# 1206PTC-TO252.net
KiCad netlist of a schematic drawn in EAGLE
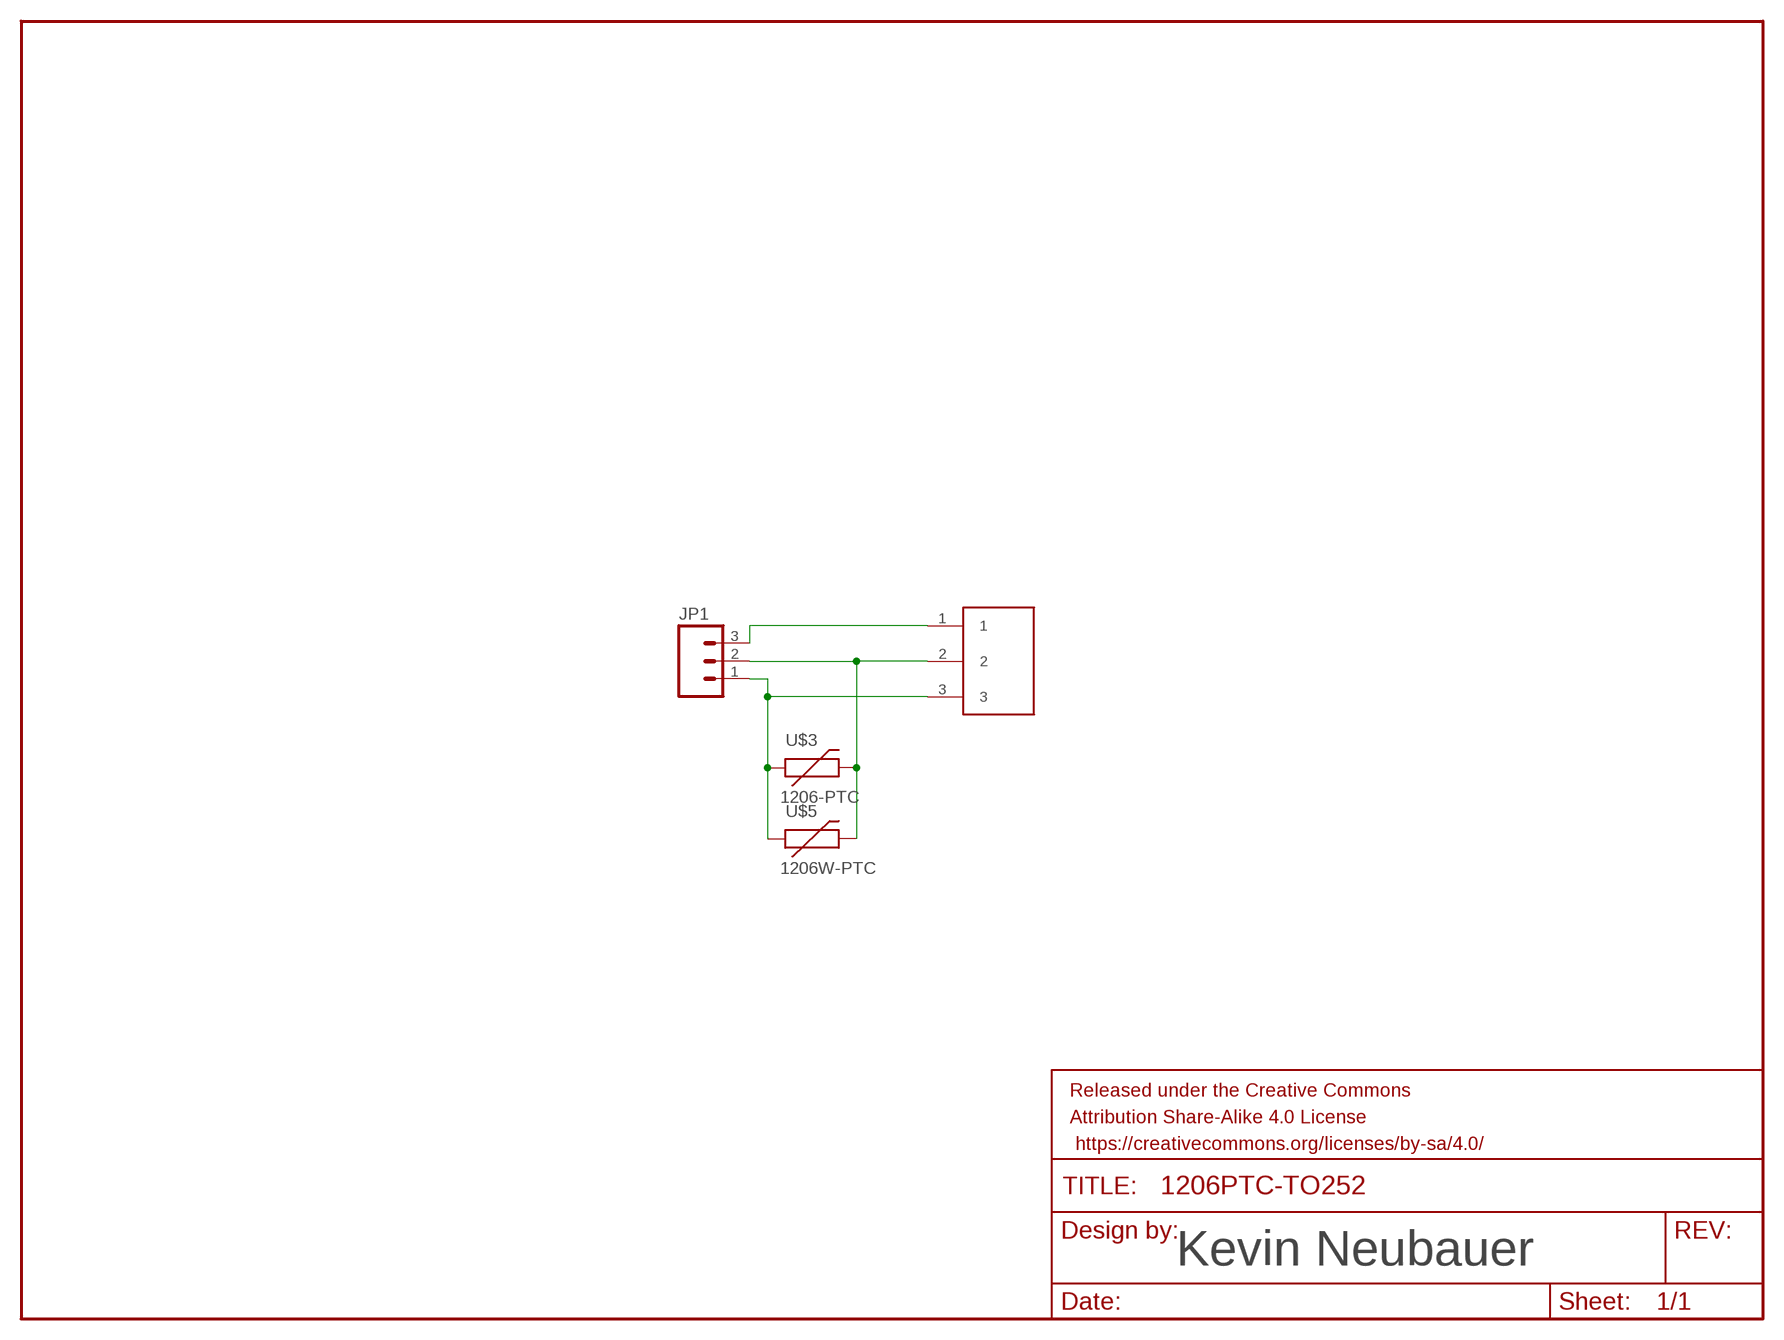
[diagram p0: schematic, sheet 1]

(export (version "E")
  (design (tool "Eeschema 10.0.6"))
  (components
    (comp (ref "FRAME1")
      (value "FRAME-LETTER")
      (footprint "eagle-import:CREATIVE_COMMONS")
      (libsource (lib "eagle-import") (part "FRAME-LETTER"))
    )
    (comp (ref "JP1")
      (value "M03PTH")
      (footprint "eagle-import:1X03")
      (libsource (lib "eagle-import") (part "M03PTH"))
    )
    (comp (ref "U$3")
      (value "1206-PTC")
      (footprint "eagle-import:PTC-1206")
      (libsource (lib "eagle-import") (part "1206-PTC"))
    )
    (comp (ref "U$4")
      (value "DPAK")
      (footprint "eagle-import:DPAK")
      (libsource (lib "eagle-import") (part "DPAK"))
    )
    (comp (ref "U$5")
      (value "1206W-PTC")
      (footprint "eagle-import:PTC-1206-WIDE")
      (libsource (lib "eagle-import") (part "1206W-PTC"))
    )
  )
  (nets
    (net (code "1") (name "Net-(JP1-Pad1)") (class "Default")
      (node (ref "JP1") (pin "1") (pinfunction "1_1") (pintype "passive"))
      (node (ref "U$3") (pin "1") (pinfunction "1_1") (pintype "bidirectional"))
      (node (ref "U$4") (pin "3") (pinfunction "3_3") (pintype "bidirectional"))
      (node (ref "U$5") (pin "1") (pinfunction "1_1") (pintype "bidirectional"))
    )
    (net (code "2") (name "Net-(JP1-Pad2)") (class "Default")
      (node (ref "JP1") (pin "2") (pinfunction "2_2") (pintype "passive"))
      (node (ref "U$3") (pin "2") (pinfunction "2_2") (pintype "bidirectional"))
      (node (ref "U$4") (pin "2") (pinfunction "2_2") (pintype "bidirectional"))
      (node (ref "U$5") (pin "2") (pinfunction "2_2") (pintype "bidirectional"))
    )
    (net (code "3") (name "Net-(JP1-Pad3)") (class "Default")
      (node (ref "JP1") (pin "3") (pinfunction "3_3") (pintype "passive"))
      (node (ref "U$4") (pin "1") (pinfunction "1_1") (pintype "bidirectional"))
    )
  )
)
